# 3_Interface_Charge_RBF.net
KiCad netlist of a schematic drawn in Altium Designer
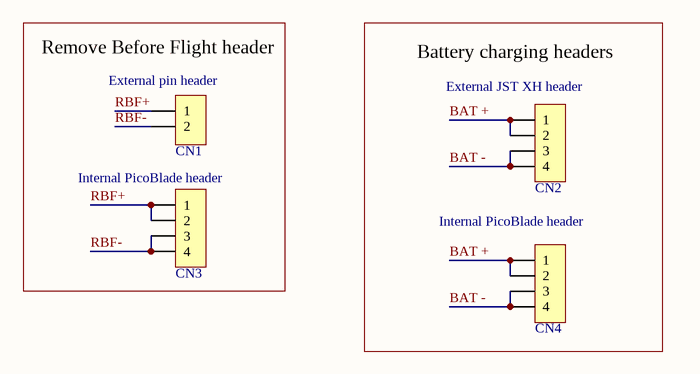
[diagram p0: 3_Interface_Charge_RBF.SchDoc]

(export (version "E")
  (design (tool "Eeschema 10.0.6"))
  (components
    (comp (ref "CN1")
      (value "M20-9990245")
      (footprint "CONN HEADER VERT 2POS 2.54mm")
      (description "M20 HDR, PIN, SIL, VERT, 2W")
      (fields (field (name "MANUFACTURER") "Harwin") (field (name "VOLTAGE") "50V"))
      (libsource (lib "IB_floripasat2") (part "M20-9990245"))
    )
    (comp (ref "CN2")
      (value "B4B-XH-A(LF)(SN)")
      (footprint "B4B-XH-A(LF)(SN)")
      (fields (field (name "MANUFACTURER") "JST"))
      (libsource (lib "IB_floripasat2") (part "B4B-XH-A(LF)(SN)"))
    )
    (comp (ref "CN3")
      (value "0533980471")
      (footprint "PICO BLADE 0533980471")
      (description "CONN HEADER SMD 4POS 1.25MM")
      (fields (field (name "MANUFACTURER") "Molex"))
      (libsource (lib "IB_floripasat2") (part "0533980471"))
    )
    (comp (ref "CN4")
      (value "0533980471")
      (footprint "PICO BLADE 0533980471")
      (description "CONN HEADER SMD 4POS 1.25MM")
      (fields (field (name "MANUFACTURER") "Molex"))
      (libsource (lib "IB_floripasat2") (part "0533980471"))
    )
  )
  (nets
    (net (code "1") (name "/BAT +") (class "Default")
      (node (ref "CN2") (pin "1") (pinfunction "1_1") (pintype "passive"))
      (node (ref "CN2") (pin "2") (pinfunction "2_2") (pintype "passive"))
      (node (ref "CN4") (pin "1") (pinfunction "1_1") (pintype "passive"))
      (node (ref "CN4") (pin "2") (pinfunction "2_2") (pintype "passive"))
    )
    (net (code "2") (name "/BAT -") (class "Default")
      (node (ref "CN2") (pin "3") (pinfunction "3_3") (pintype "passive"))
      (node (ref "CN2") (pin "4") (pinfunction "4_4") (pintype "passive"))
      (node (ref "CN4") (pin "3") (pinfunction "3_3") (pintype "passive"))
      (node (ref "CN4") (pin "4") (pinfunction "4_4") (pintype "passive"))
    )
    (net (code "3") (name "/RBF+") (class "Default")
      (node (ref "CN1") (pin "1") (pinfunction "1_1") (pintype "passive"))
      (node (ref "CN3") (pin "1") (pinfunction "1_1") (pintype "passive"))
      (node (ref "CN3") (pin "2") (pinfunction "2_2") (pintype "passive"))
    )
    (net (code "4") (name "/RBF-") (class "Default")
      (node (ref "CN1") (pin "2") (pinfunction "2_2") (pintype "passive"))
      (node (ref "CN3") (pin "3") (pinfunction "3_3") (pintype "passive"))
      (node (ref "CN3") (pin "4") (pinfunction "4_4") (pintype "passive"))
    )
  )
)
